# LAPPA-2020.net
KiCad netlist of a schematic drawn in Altium Designer
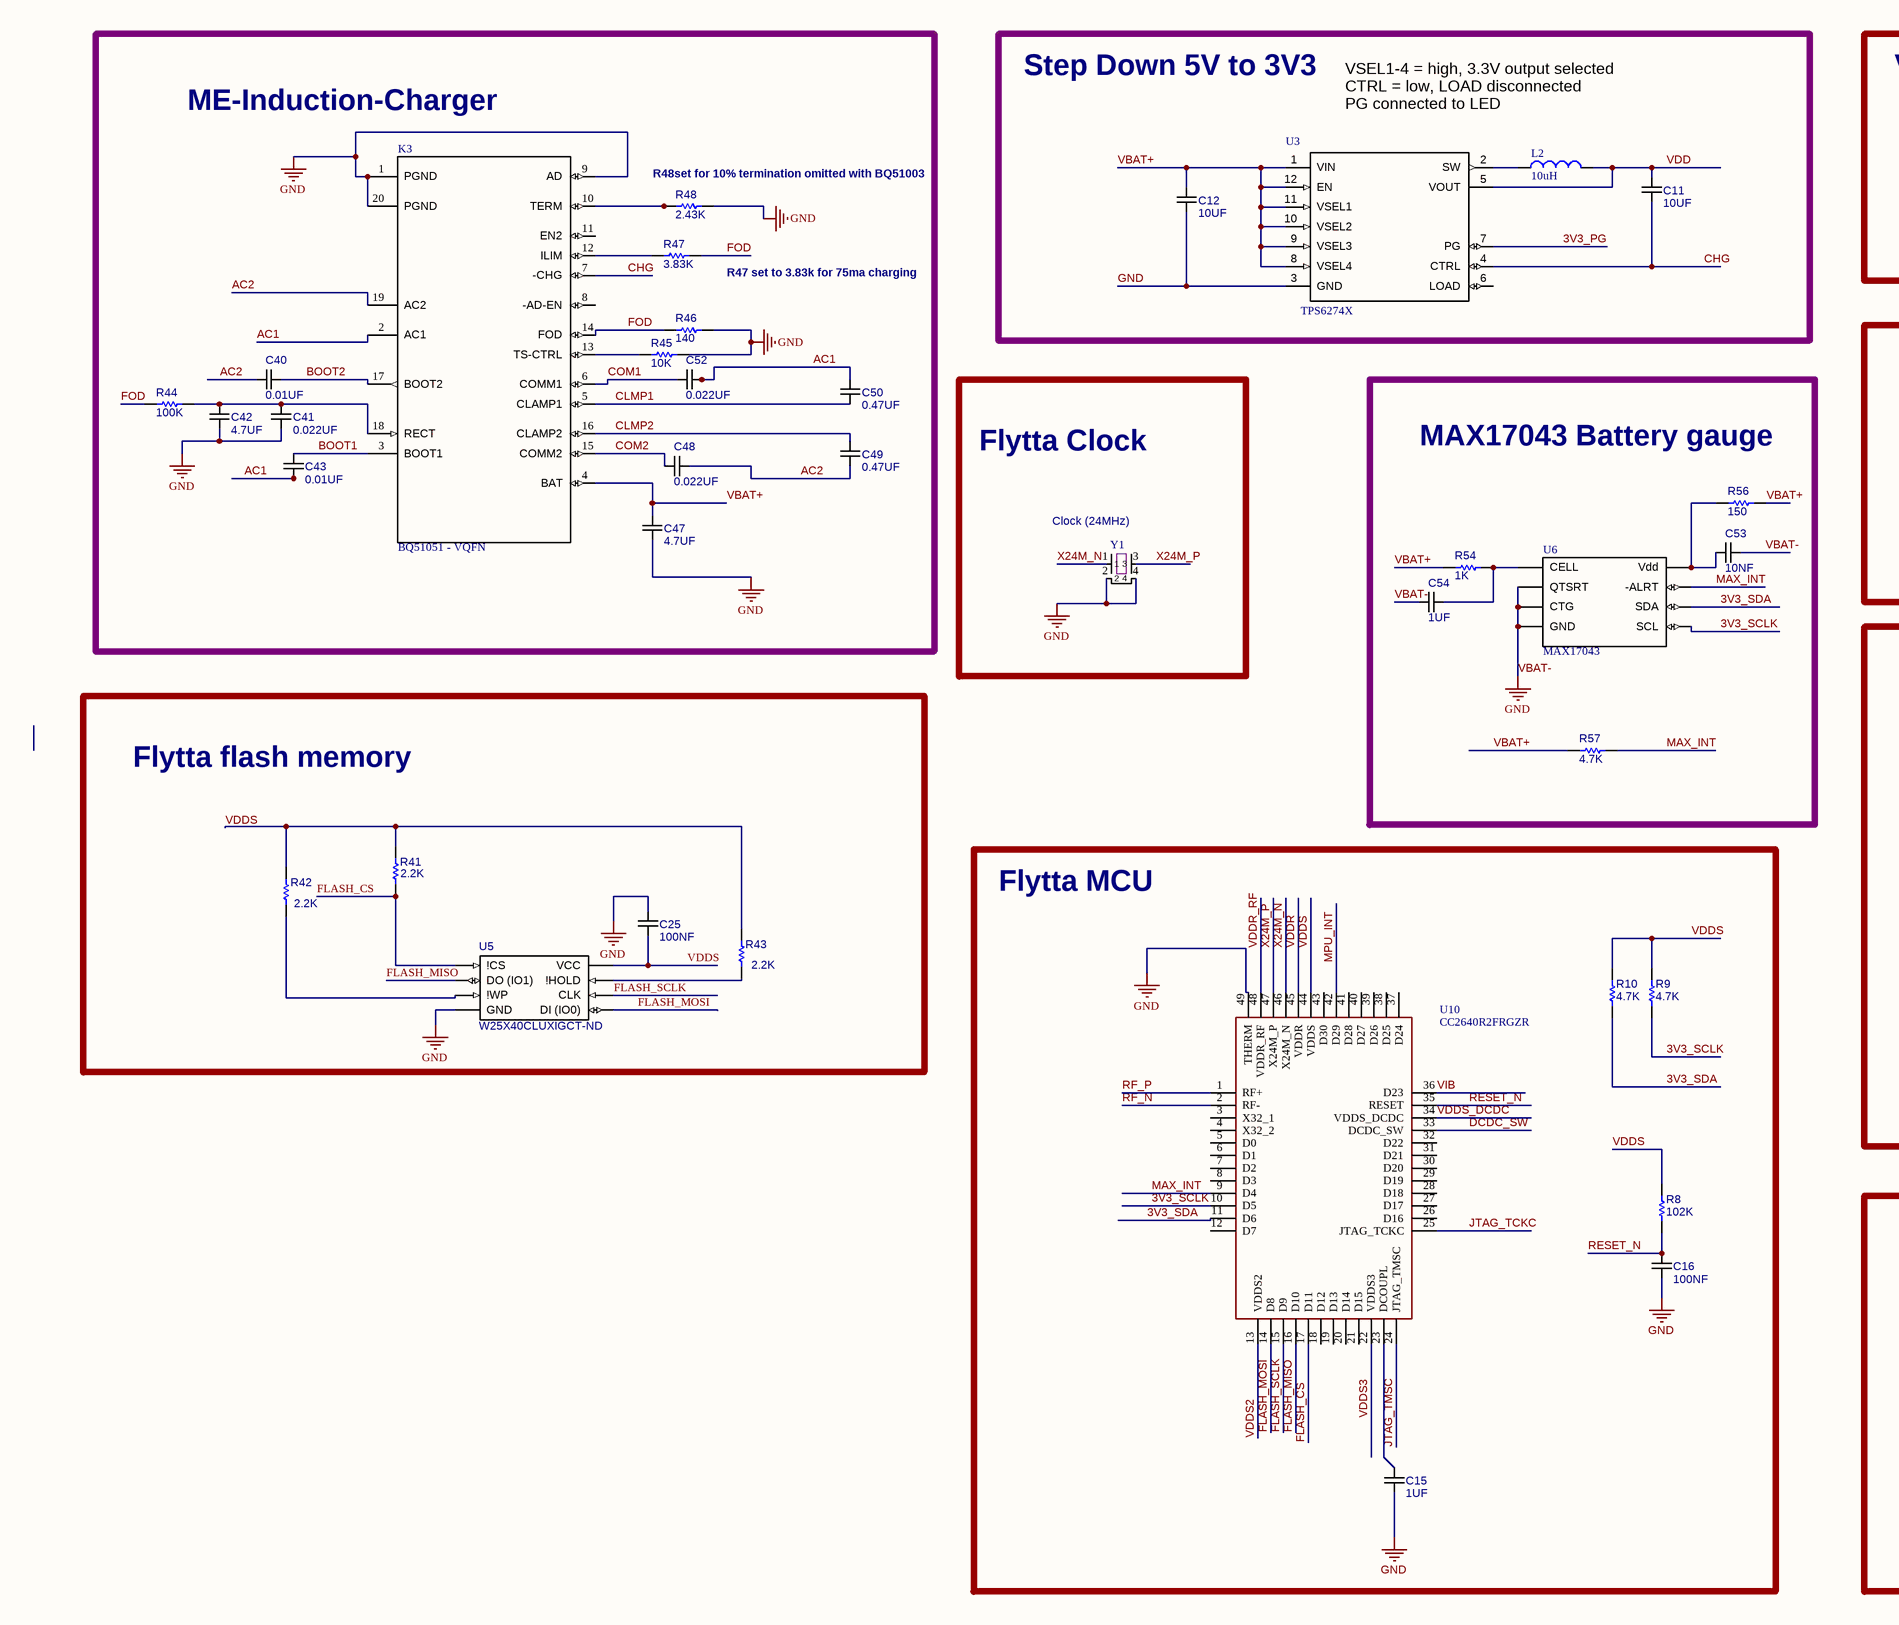
[diagram p0: LAPPA-2020.SchDoc, left]
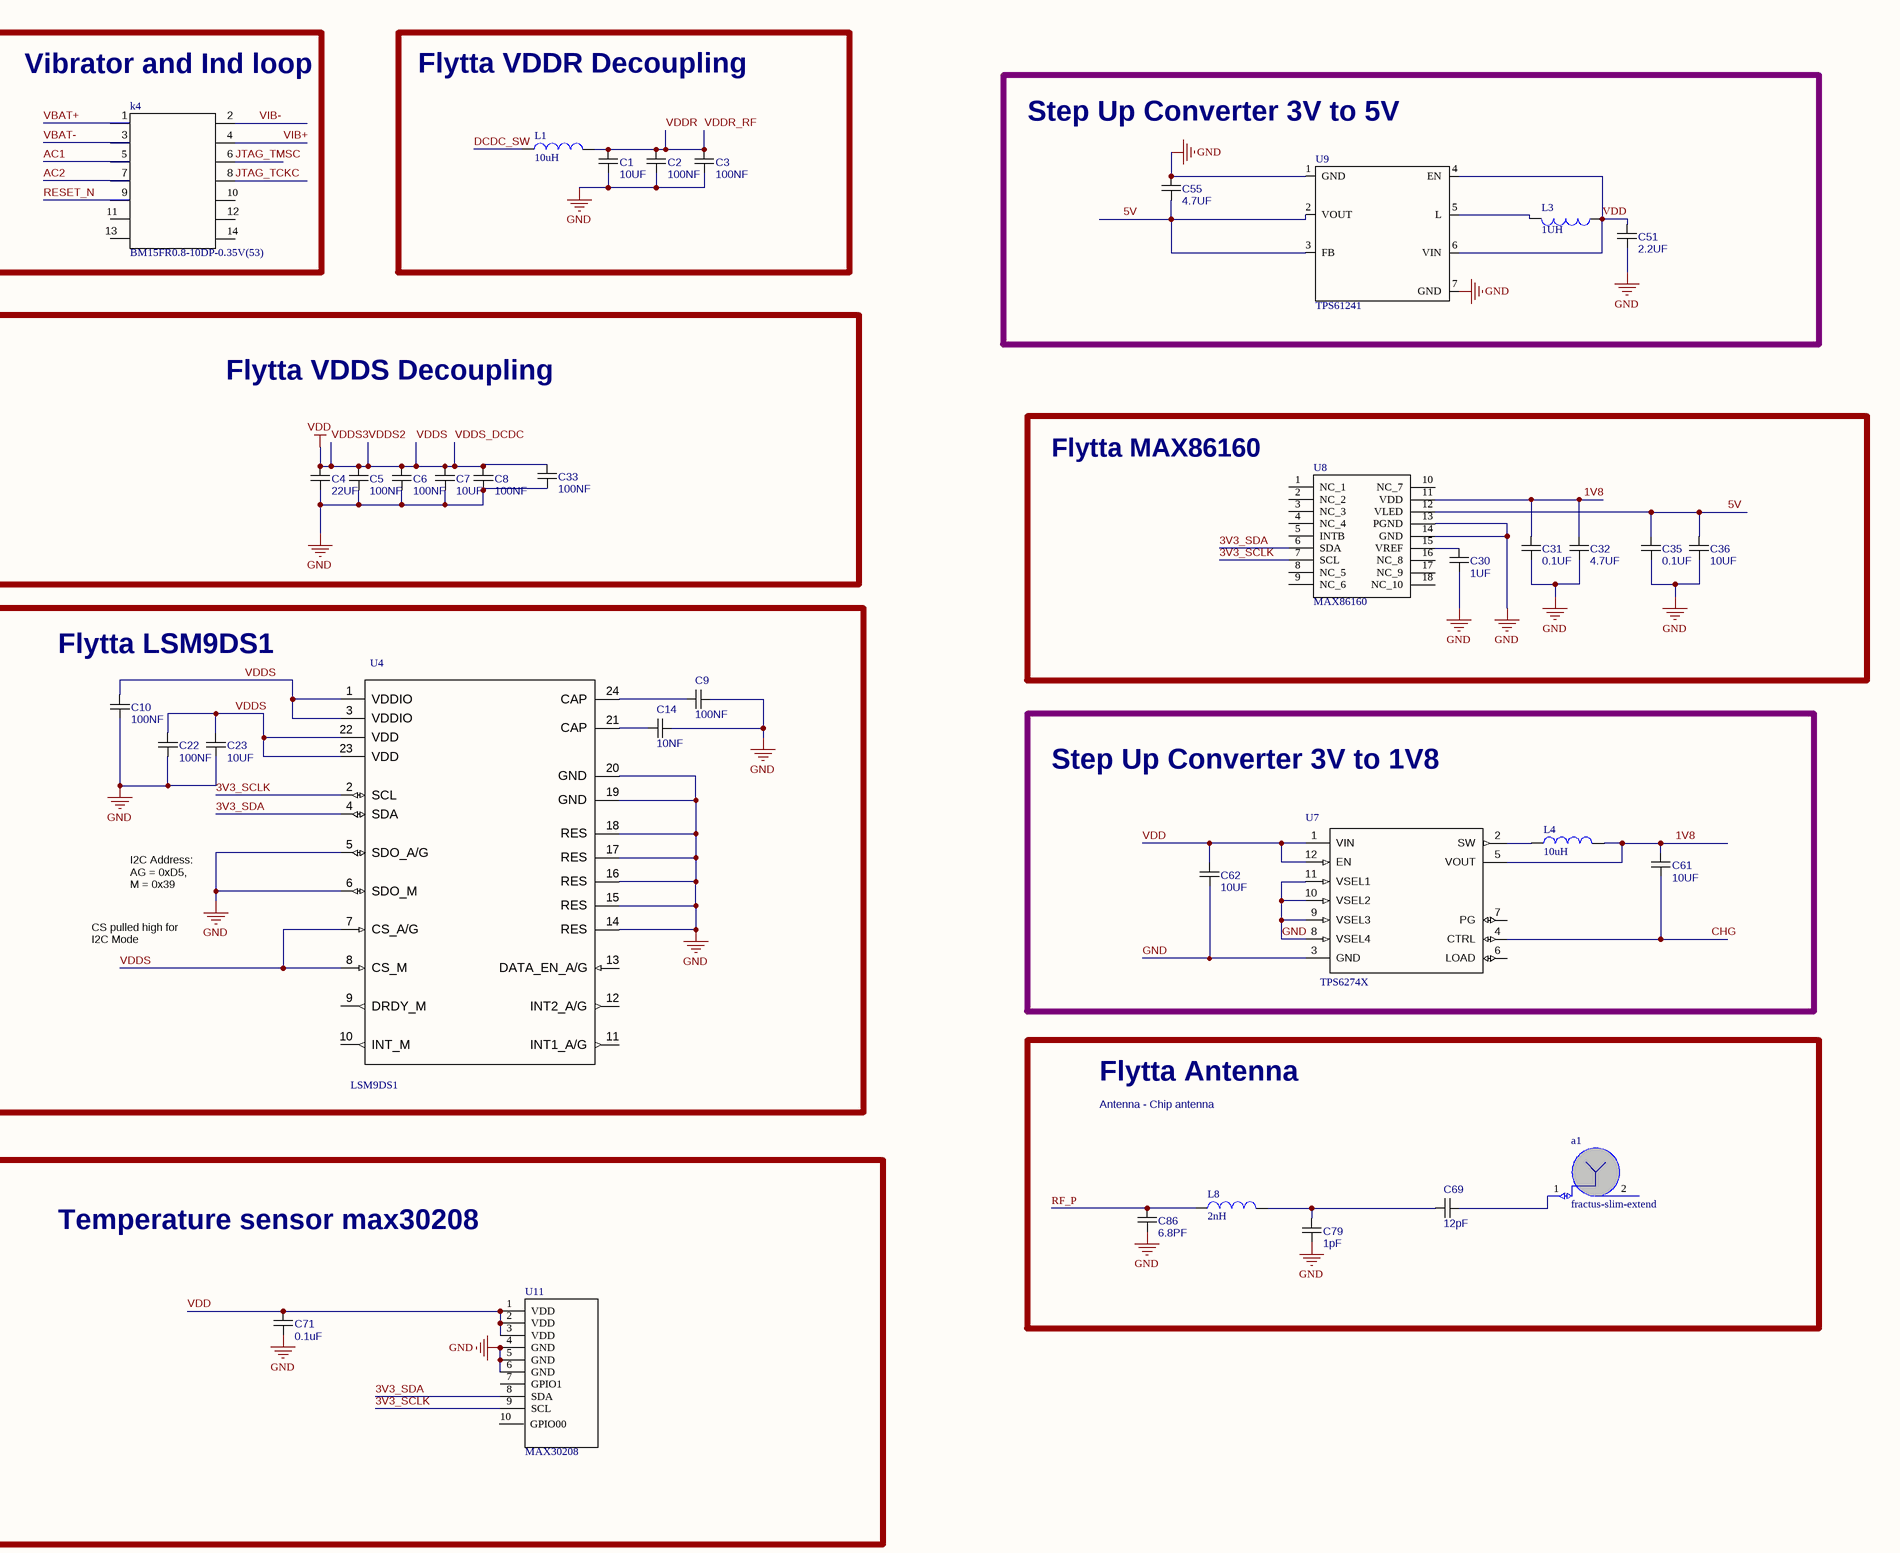
[diagram p1: LAPPA-2020.SchDoc, right]

(export (version "E")
  (design (tool "Eeschema 10.0.6"))
  (components
    (comp (ref "a1")
      (value "fractus-slim-extend")
      (footprint "fractus-chip-antenna")
      (description "fractus ti chip antenna")
      (libsource (lib "MedEngineSchematicLib") (part "fractus-chip-antenna"))
    )
    (comp (ref "C1")
      (value "10UF")
      (footprint "Passive (0402, 1005)")
      (description "Ceramic chip capacitor")
      (libsource (lib "MedEngineSchematicLib") (part "Capacitor"))
    )
    (comp (ref "C2")
      (value "100NF")
      (footprint "Passive (0402, 1005)")
      (description "Ceramic chip capacitor")
      (libsource (lib "MedEngineSchematicLib") (part "Capacitor"))
    )
    (comp (ref "C3")
      (value "100NF")
      (footprint "Passive (0402, 1005)")
      (description "Ceramic chip capacitor")
      (libsource (lib "MedEngineSchematicLib") (part "Capacitor"))
    )
    (comp (ref "C4")
      (value "22UF")
      (footprint "Passive (0402, 1005)")
      (description "Ceramic chip capacitor")
      (libsource (lib "MedEngineSchematicLib") (part "Capacitor"))
    )
    (comp (ref "C5")
      (value "100NF")
      (footprint "Passive (0402, 1005)")
      (description "Ceramic chip capacitor")
      (libsource (lib "MedEngineSchematicLib") (part "Capacitor"))
    )
    (comp (ref "C6")
      (value "100NF")
      (footprint "Passive (0402, 1005)")
      (description "Ceramic chip capacitor")
      (libsource (lib "MedEngineSchematicLib") (part "Capacitor"))
    )
    (comp (ref "C7")
      (value "10UF")
      (footprint "Passive (0402, 1005)")
      (description "Ceramic chip capacitor")
      (libsource (lib "MedEngineSchematicLib") (part "Capacitor"))
    )
    (comp (ref "C8")
      (value "100NF")
      (footprint "Passive (0402, 1005)")
      (description "Ceramic chip capacitor")
      (libsource (lib "MedEngineSchematicLib") (part "Capacitor"))
    )
    (comp (ref "C9")
      (value "100NF")
      (footprint "Passive (0402, 1005)")
      (description "Ceramic chip capacitor")
      (libsource (lib "MedEngineSchematicLib") (part "Capacitor"))
    )
    (comp (ref "C10")
      (value "100NF")
      (footprint "Passive (0402, 1005)")
      (description "Ceramic chip capacitor")
      (libsource (lib "MedEngineSchematicLib") (part "Capacitor"))
    )
    (comp (ref "C11")
      (value "10UF")
      (footprint "Passive (0402, 1005)")
      (description "Ceramic chip capacitor")
      (libsource (lib "MedEngineSchematicLib") (part "Capacitor"))
    )
    (comp (ref "C12")
      (value "10UF")
      (footprint "Passive (0402, 1005)")
      (description "Ceramic chip capacitor")
      (libsource (lib "MedEngineSchematicLib") (part "Capacitor"))
    )
    (comp (ref "C14")
      (value "10NF")
      (footprint "Passive (0402, 1005)")
      (description "Ceramic chip capacitor")
      (libsource (lib "MedEngineSchematicLib") (part "Capacitor"))
    )
    (comp (ref "C15")
      (value "1UF")
      (footprint "Passive (0402, 1005)")
      (description "Ceramic chip capacitor")
      (libsource (lib "MedEngineSchematicLib") (part "Capacitor"))
    )
    (comp (ref "C16")
      (value "100NF")
      (footprint "Passive (0402, 1005)")
      (description "Ceramic chip capacitor")
      (libsource (lib "MedEngineSchematicLib") (part "Capacitor"))
    )
    (comp (ref "C22")
      (value "100NF")
      (footprint "Passive (0402, 1005)")
      (description "Ceramic chip capacitor")
      (libsource (lib "MedEngineSchematicLib") (part "Capacitor"))
    )
    (comp (ref "C23")
      (value "10UF")
      (footprint "Passive (0402, 1005)")
      (description "Ceramic chip capacitor")
      (libsource (lib "MedEngineSchematicLib") (part "Capacitor"))
    )
    (comp (ref "C25")
      (value "100NF")
      (footprint "Passive (0402, 1005)")
      (description "Ceramic chip capacitor")
      (libsource (lib "MedEngineSchematicLib") (part "Capacitor"))
    )
    (comp (ref "C30")
      (value "1UF")
      (footprint "Passive (0402, 1005)")
      (description "Ceramic chip capacitor")
      (libsource (lib "MedEngineSchematicLib") (part "Capacitor"))
    )
    (comp (ref "C31")
      (value "0.1UF")
      (footprint "Passive (0402, 1005)")
      (description "Ceramic chip capacitor")
      (libsource (lib "MedEngineSchematicLib") (part "Capacitor"))
    )
    (comp (ref "C32")
      (value "4.7UF")
      (footprint "Passive (0402, 1005)")
      (description "Ceramic chip capacitor")
      (libsource (lib "MedEngineSchematicLib") (part "Capacitor"))
    )
    (comp (ref "C33")
      (value "100NF")
      (footprint "Passive (0402, 1005)")
      (description "Ceramic chip capacitor")
      (libsource (lib "MedEngineSchematicLib") (part "Capacitor"))
    )
    (comp (ref "C35")
      (value "0.1UF")
      (footprint "Passive (0402, 1005)")
      (description "Ceramic chip capacitor")
      (libsource (lib "MedEngineSchematicLib") (part "Capacitor"))
    )
    (comp (ref "C36")
      (value "10UF")
      (footprint "Passive (0402, 1005)")
      (description "Ceramic chip capacitor")
      (libsource (lib "MedEngineSchematicLib") (part "Capacitor"))
    )
    (comp (ref "C40")
      (value "0.01UF")
      (footprint "Passive (0402, 1005)")
      (description "Ceramic chip capacitor")
      (libsource (lib "MedEngineSchematicLib") (part "Capacitor"))
    )
    (comp (ref "C41")
      (value "0.022UF")
      (footprint "Passive (0402, 1005)")
      (description "Ceramic chip capacitor")
      (libsource (lib "MedEngineSchematicLib") (part "Capacitor"))
    )
    (comp (ref "C42")
      (value "4.7UF")
      (footprint "Passive (0402, 1005)")
      (description "Ceramic chip capacitor")
      (libsource (lib "MedEngineSchematicLib") (part "Capacitor"))
    )
    (comp (ref "C43")
      (value "0.01UF")
      (footprint "Passive (0402, 1005)")
      (description "Ceramic chip capacitor")
      (libsource (lib "MedEngineSchematicLib") (part "Capacitor"))
    )
    (comp (ref "C47")
      (value "4.7UF")
      (footprint "Passive (0402, 1005)")
      (description "Ceramic chip capacitor")
      (libsource (lib "MedEngineSchematicLib") (part "Capacitor"))
    )
    (comp (ref "C48")
      (value "0.022UF")
      (footprint "Passive (0402, 1005)")
      (description "Ceramic chip capacitor")
      (libsource (lib "MedEngineSchematicLib") (part "Capacitor"))
    )
    (comp (ref "C49")
      (value "0.47UF")
      (footprint "Passive (0402, 1005)")
      (description "Ceramic chip capacitor")
      (libsource (lib "MedEngineSchematicLib") (part "Capacitor"))
    )
    (comp (ref "C50")
      (value "0.47UF")
      (footprint "Passive (0402, 1005)")
      (description "Ceramic chip capacitor")
      (libsource (lib "MedEngineSchematicLib") (part "Capacitor"))
    )
    (comp (ref "C51")
      (value "2.2UF")
      (footprint "Passive (0402, 1005)")
      (description "Ceramic chip capacitor")
      (libsource (lib "MedEngineSchematicLib") (part "Capacitor"))
    )
    (comp (ref "C52")
      (value "0.022UF")
      (footprint "Passive (0402, 1005)")
      (description "Ceramic chip capacitor")
      (libsource (lib "MedEngineSchematicLib") (part "Capacitor"))
    )
    (comp (ref "C53")
      (value "10NF")
      (footprint "Passive (0402, 1005)")
      (description "Ceramic chip capacitor")
      (libsource (lib "MedEngineSchematicLib") (part "Capacitor"))
    )
    (comp (ref "C54")
      (value "1UF")
      (footprint "Passive (0402, 1005)")
      (description "Ceramic chip capacitor")
      (libsource (lib "MedEngineSchematicLib") (part "Capacitor"))
    )
    (comp (ref "C55")
      (value "4.7UF")
      (footprint "Passive (0402, 1005)")
      (description "Ceramic chip capacitor")
      (libsource (lib "MedEngineSchematicLib") (part "Capacitor"))
    )
    (comp (ref "C61")
      (value "10UF")
      (footprint "Passive (0402, 1005)")
      (description "Ceramic chip capacitor")
      (libsource (lib "MedEngineSchematicLib") (part "Capacitor"))
    )
    (comp (ref "C62")
      (value "10UF")
      (footprint "Passive (0402, 1005)")
      (description "Ceramic chip capacitor")
      (libsource (lib "MedEngineSchematicLib") (part "Capacitor"))
    )
    (comp (ref "C69")
      (value "12pF")
      (footprint "Passive (0402, 1005)")
      (description "Ceramic chip capacitor")
      (libsource (lib "MedEngineSchematicLib") (part "Capacitor"))
    )
    (comp (ref "C71")
      (value "0.1uF")
      (footprint "Passive (0402, 1005)")
      (description "Ceramic chip capacitor")
      (libsource (lib "MedEngineSchematicLib") (part "Capacitor"))
    )
    (comp (ref "C79")
      (value "1pF")
      (footprint "Passive (0402, 1005)")
      (description "Ceramic chip capacitor")
      (libsource (lib "MedEngineSchematicLib") (part "Capacitor"))
    )
    (comp (ref "C86")
      (value "6.8PF")
      (footprint "Passive (0402, 1005)")
      (description "Ceramic chip capacitor")
      (libsource (lib "MedEngineSchematicLib") (part "Capacitor"))
    )
    (comp (ref "K3")
      (value "BQ51051 - VQFN")
      (footprint "bq51051 - vqfn")
      (libsource (lib "MedEngineSchematicLib") (part "BQ51051 - VQFN"))
    )
    (comp (ref "k4")
      (value "BM15FR0.8-10DP-0.35V(53)")
      (footprint "BM15-Header")
      (libsource (lib "MedEngineSchematicLib") (part "bm15"))
    )
    (comp (ref "L1")
      (value "10uH")
      (footprint "Passive (0603, 1608)")
      (description "Inductor")
      (fields (field (name "PUBLISHER") "Altium Limited"))
      (libsource (lib "MedEngineSchematicLib") (part "Inductor"))
    )
    (comp (ref "L2")
      (value "10uH")
      (footprint "Passive (0603, 1608)")
      (description "Inductor")
      (fields (field (name "PUBLISHER") "Altium Limited"))
      (libsource (lib "MedEngineSchematicLib") (part "Inductor"))
    )
    (comp (ref "L3")
      (value "1UH")
      (footprint "Passive (0603, 1608)")
      (description "Inductor")
      (fields (field (name "PUBLISHER") "Altium Limited"))
      (libsource (lib "MedEngineSchematicLib") (part "Inductor"))
    )
    (comp (ref "L4")
      (value "10uH")
      (footprint "Passive (0603, 1608)")
      (description "Inductor")
      (fields (field (name "PUBLISHER") "Altium Limited"))
      (libsource (lib "MedEngineSchematicLib") (part "Inductor"))
    )
    (comp (ref "L8")
      (value "2nH")
      (footprint "Passive (0402, 1005)")
      (description "Inductor")
      (fields (field (name "PUBLISHER") "Altium Limited"))
      (libsource (lib "MedEngineSchematicLib") (part "Inductor"))
    )
    (comp (ref "R8")
      (value "102K")
      (footprint "Passive (0402, 1005)")
      (description "Resistor")
      (libsource (lib "MedEngineSchematicLib") (part "Resistor"))
    )
    (comp (ref "R9")
      (value "4.7K")
      (footprint "Passive (0402, 1005)")
      (description "Resistor")
      (libsource (lib "MedEngineSchematicLib") (part "Resistor"))
    )
    (comp (ref "R10")
      (value "4.7K")
      (footprint "Passive (0402, 1005)")
      (description "Resistor")
      (libsource (lib "MedEngineSchematicLib") (part "Resistor"))
    )
    (comp (ref "R41")
      (value "2.2K")
      (footprint "Passive (0402, 1005)")
      (description "Resistor")
      (libsource (lib "MedEngineSchematicLib") (part "Resistor"))
    )
    (comp (ref "R42")
      (value "2.2K")
      (footprint "Passive (0402, 1005)")
      (description "Resistor")
      (libsource (lib "MedEngineSchematicLib") (part "Resistor"))
    )
    (comp (ref "R43")
      (value "2.2K")
      (footprint "Passive (0402, 1005)")
      (description "Resistor")
      (libsource (lib "MedEngineSchematicLib") (part "Resistor"))
    )
    (comp (ref "R44")
      (value "100K")
      (footprint "Passive (0402, 1005)")
      (description "Resistor")
      (libsource (lib "MedEngineSchematicLib") (part "Resistor"))
    )
    (comp (ref "R45")
      (value "10K")
      (footprint "Passive (0402, 1005)")
      (description "Resistor")
      (libsource (lib "MedEngineSchematicLib") (part "Resistor"))
    )
    (comp (ref "R46")
      (value "140")
      (footprint "Passive (0402, 1005)")
      (description "Resistor")
      (libsource (lib "MedEngineSchematicLib") (part "Resistor"))
    )
    (comp (ref "R47")
      (value "3.83K")
      (footprint "Passive (0402, 1005)")
      (description "Resistor")
      (libsource (lib "MedEngineSchematicLib") (part "Resistor"))
    )
    (comp (ref "R48")
      (value "2.43K")
      (footprint "Passive (0402, 1005)")
      (description "Resistor")
      (libsource (lib "MedEngineSchematicLib") (part "Resistor"))
    )
    (comp (ref "R54")
      (value "1K")
      (footprint "Passive (0402, 1005)")
      (description "Resistor")
      (libsource (lib "MedEngineSchematicLib") (part "Resistor"))
    )
    (comp (ref "R56")
      (value "150")
      (footprint "Passive (0402, 1005)")
      (description "Resistor")
      (libsource (lib "MedEngineSchematicLib") (part "Resistor"))
    )
    (comp (ref "R57")
      (value "4.7K")
      (footprint "Passive (0402, 1005)")
      (description "Resistor")
      (libsource (lib "MedEngineSchematicLib") (part "Resistor"))
    )
    (comp (ref "U3")
      (value "TPS6274X")
      (footprint "TPS6274")
      (description "Step down converter")
      (libsource (lib "MedEngineSchematicLib") (part "TPS6274X"))
    )
    (comp (ref "U4")
      (value "LSM9DS1")
      (footprint "LSM9DS1")
      (description "9DOF, Accel, Gyro, Mag")
      (fields (field (name "MF") "Microchip") (field (name "MP") "MCP73871-3CAI/ML"))
      (libsource (lib "MedEngineSchematicLib") (part "LSM9DS1"))
    )
    (comp (ref "U5")
      (value "W25X40CLUXIGCT-ND")
      (footprint "USON 2x3")
      (libsource (lib "MedEngineSchematicLib") (part "W25X40CLUXIGCT-ND"))
    )
    (comp (ref "U6")
      (value "MAX17043")
      (footprint "MAX17043")
      (description "I2C battery gauge")
      (libsource (lib "MedEngineSchematicLib") (part "MAX17043"))
    )
    (comp (ref "U7")
      (value "TPS6274X")
      (footprint "TPS6274")
      (description "Step down converter")
      (libsource (lib "MedEngineSchematicLib") (part "TPS6274X"))
    )
    (comp (ref "U8")
      (value "MAX86160")
      (footprint "MAX86160")
      (libsource (lib "MedEngineSchematicLib") (part "MAX86160"))
    )
    (comp (ref "U9")
      (value "TPS61241")
      (footprint "TPS61241")
      (libsource (lib "MedEngineSchematicLib") (part "TPS61241"))
    )
    (comp (ref "U10")
      (value "CC2640R2FRGZR")
      (footprint "CC2640R2FRGZR")
      (libsource (lib "MedEngineSchematicLib") (part "CC2640R2FRGZR"))
    )
    (comp (ref "U11")
      (value "MAX30208")
      (footprint "MAX30208")
      (libsource (lib "MedEngineSchematicLib") (part "MAX30208"))
    )
    (comp (ref "Y1")
      (value "24MHz crystal")
      (footprint "TSX-3225")
      (libsource (lib "TSX3225") (part "TSX-3225"))
    )
  )
  (nets
    (net (code "1") (name "/1V8") (class "Default")
      (node (ref "C31") (pin "2") (pinfunction "2_2") (pintype "passive"))
      (node (ref "C32") (pin "2") (pinfunction "2_2") (pintype "passive"))
      (node (ref "C61") (pin "2") (pinfunction "2_2") (pintype "passive"))
      (node (ref "L4") (pin "2") (pinfunction "2_2") (pintype "passive"))
      (node (ref "U7") (pin "5") (pinfunction "VOUT_5") (pintype "power_in"))
      (node (ref "U8") (pin "11") (pinfunction "VDD_11") (pintype "passive"))
    )
    (net (code "2") (name "/3V3_PG") (class "Default")
      (node (ref "U3") (pin "7") (pinfunction "PG_7") (pintype "bidirectional"))
    )
    (net (code "3") (name "/3V3_SCLK") (class "Default")
      (node (ref "R9") (pin "1") (pinfunction "1_1") (pintype "passive"))
      (node (ref "U10") (pin "10") (pinfunction "D5_10") (pintype "passive"))
      (node (ref "U11") (pin "9") (pinfunction "SCL_9") (pintype "passive"))
      (node (ref "U4") (pin "2") (pinfunction "SCL_2") (pintype "bidirectional"))
      (node (ref "U6") (pin "A2") (pinfunction "SCL_A2") (pintype "bidirectional"))
      (node (ref "U8") (pin "7") (pinfunction "SCL_7") (pintype "passive"))
    )
    (net (code "4") (name "/3V3_SDA") (class "Default")
      (node (ref "R10") (pin "1") (pinfunction "1_1") (pintype "passive"))
      (node (ref "U10") (pin "11") (pinfunction "D6_11") (pintype "passive"))
      (node (ref "U11") (pin "8") (pinfunction "SDA_8") (pintype "passive"))
      (node (ref "U4") (pin "4") (pinfunction "SDA_4") (pintype "bidirectional"))
      (node (ref "U6") (pin "A1") (pinfunction "SDA_A1") (pintype "bidirectional"))
      (node (ref "U8") (pin "6") (pinfunction "SDA_6") (pintype "passive"))
    )
    (net (code "5") (name "/5V") (class "Default")
      (node (ref "C35") (pin "2") (pinfunction "2_2") (pintype "passive"))
      (node (ref "C36") (pin "2") (pinfunction "2_2") (pintype "passive"))
      (node (ref "C55") (pin "1") (pinfunction "1_1") (pintype "passive"))
      (node (ref "U8") (pin "12") (pinfunction "VLED_12") (pintype "passive"))
      (node (ref "U9") (pin "2") (pinfunction "VOUT_2") (pintype "passive"))
      (node (ref "U9") (pin "3") (pinfunction "FB_3") (pintype "passive"))
    )
    (net (code "6") (name "/AC1") (class "Default")
      (node (ref "C43") (pin "2") (pinfunction "2_2") (pintype "passive"))
      (node (ref "C50") (pin "1") (pinfunction "1_1") (pintype "passive"))
      (node (ref "C52") (pin "2") (pinfunction "2_2") (pintype "passive"))
      (node (ref "K3") (pin "2") (pinfunction "AC1_2") (pintype "passive"))
      (node (ref "k4") (pin "5") (pintype "power_in"))
    )
    (net (code "7") (name "/AC2") (class "Default")
      (node (ref "C40") (pin "2") (pinfunction "2_2") (pintype "passive"))
      (node (ref "C48") (pin "2") (pinfunction "2_2") (pintype "passive"))
      (node (ref "C49") (pin "2") (pinfunction "2_2") (pintype "passive"))
      (node (ref "K3") (pin "19") (pinfunction "AC2_19") (pintype "power_in"))
      (node (ref "k4") (pin "7") (pintype "passive"))
    )
    (net (code "8") (name "/BOOT1") (class "Default")
      (node (ref "C43") (pin "1") (pinfunction "1_1") (pintype "passive"))
      (node (ref "K3") (pin "3") (pinfunction "BOOT1_3") (pintype "passive"))
    )
    (net (code "9") (name "/BOOT2") (class "Default")
      (node (ref "C40") (pin "1") (pinfunction "1_1") (pintype "passive"))
      (node (ref "K3") (pin "17") (pinfunction "BOOT2_17") (pintype "output"))
    )
    (net (code "10") (name "/CHG") (class "Default")
      (node (ref "C11") (pin "1") (pinfunction "1_1") (pintype "passive"))
      (node (ref "C61") (pin "1") (pinfunction "1_1") (pintype "passive"))
      (node (ref "K3") (pin "7") (pinfunction "-CHG_7") (pintype "bidirectional"))
      (node (ref "U3") (pin "4") (pinfunction "CTRL_4") (pintype "bidirectional"))
      (node (ref "U7") (pin "4") (pinfunction "CTRL_4") (pintype "bidirectional"))
    )
    (net (code "11") (name "/CLMP1") (class "Default")
      (node (ref "C50") (pin "2") (pinfunction "2_2") (pintype "passive"))
      (node (ref "K3") (pin "5") (pinfunction "CLAMP1_5") (pintype "bidirectional"))
    )
    (net (code "12") (name "/CLMP2") (class "Default")
      (node (ref "C49") (pin "1") (pinfunction "1_1") (pintype "passive"))
      (node (ref "K3") (pin "16") (pinfunction "CLAMP2_16") (pintype "bidirectional"))
    )
    (net (code "13") (name "/COM1") (class "Default")
      (node (ref "C52") (pin "1") (pinfunction "1_1") (pintype "passive"))
      (node (ref "K3") (pin "6") (pinfunction "COMM1_6") (pintype "bidirectional"))
    )
    (net (code "14") (name "/COM2") (class "Default")
      (node (ref "C48") (pin "1") (pinfunction "1_1") (pintype "passive"))
      (node (ref "K3") (pin "15") (pinfunction "COMM2_15") (pintype "bidirectional"))
    )
    (net (code "15") (name "/DCDC_SW") (class "Default")
      (node (ref "L1") (pin "1") (pinfunction "1_1") (pintype "passive"))
      (node (ref "U10") (pin "33") (pinfunction "DCDC_SW_33") (pintype "passive"))
    )
    (net (code "16") (name "/FLASH_CS") (class "Default")
      (node (ref "R41") (pin "1") (pinfunction "1_1") (pintype "passive"))
      (node (ref "U10") (pin "17") (pinfunction "D11_17") (pintype "passive"))
      (node (ref "U5") (pin "1") (pinfunction "!CS_1") (pintype "input"))
    )
    (net (code "17") (name "/FLASH_MISO") (class "Default")
      (node (ref "U10") (pin "16") (pinfunction "D10_16") (pintype "passive"))
      (node (ref "U5") (pin "2") (pinfunction "DO_(IO1)_2") (pintype "bidirectional"))
    )
    (net (code "18") (name "/FLASH_MOSI") (class "Default")
      (node (ref "U10") (pin "14") (pinfunction "D8_14") (pintype "passive"))
      (node (ref "U5") (pin "5") (pinfunction "DI_(IO0)_5") (pintype "bidirectional"))
    )
    (net (code "19") (name "/FLASH_SCLK") (class "Default")
      (node (ref "U10") (pin "15") (pinfunction "D9_15") (pintype "passive"))
      (node (ref "U5") (pin "6") (pinfunction "CLK_6") (pintype "input"))
    )
    (net (code "20") (name "/FOD") (class "Default")
      (node (ref "K3") (pin "14") (pinfunction "FOD_14") (pintype "bidirectional"))
      (node (ref "R44") (pin "2") (pinfunction "2_2") (pintype "passive"))
      (node (ref "R46") (pin "2") (pinfunction "2_2") (pintype "passive"))
      (node (ref "R47") (pin "1") (pinfunction "1_1") (pintype "passive"))
    )
    (net (code "21") (name "/JTAG_TCKC") (class "Default")
      (node (ref "U10") (pin "25") (pinfunction "JTAG_TCKC_25") (pintype "passive"))
      (node (ref "k4") (pin "8") (pintype "power_in"))
    )
    (net (code "22") (name "/JTAG_TMSC") (class "Default")
      (node (ref "U10") (pin "24") (pinfunction "JTAG_TMSC_24") (pintype "passive"))
      (node (ref "k4") (pin "6") (pintype "power_in"))
    )
    (net (code "23") (name "/MAX_INT") (class "Default")
      (node (ref "R57") (pin "1") (pinfunction "1_1") (pintype "passive"))
      (node (ref "U10") (pin "9") (pinfunction "D4_9") (pintype "passive"))
      (node (ref "U6") (pin "C1") (pinfunction "-ALRT_C1") (pintype "bidirectional"))
    )
    (net (code "24") (name "/MPU_INT") (class "Default")
      (node (ref "U10") (pin "42") (pinfunction "D29_42") (pintype "passive"))
    )
    (net (code "25") (name "/RESET_N") (class "Default")
      (node (ref "C16") (pin "2") (pinfunction "2_2") (pintype "passive"))
      (node (ref "R8") (pin "1") (pinfunction "1_1") (pintype "passive"))
      (node (ref "U10") (pin "35") (pinfunction "RESET_35") (pintype "passive"))
      (node (ref "k4") (pin "9") (pintype "passive"))
    )
    (net (code "26") (name "/RF_N") (class "Default")
      (node (ref "U10") (pin "2") (pinfunction "RF-_2") (pintype "passive"))
    )
    (net (code "27") (name "/RF_P") (class "Default")
      (node (ref "C86") (pin "2") (pinfunction "2_2") (pintype "passive"))
      (node (ref "L8") (pin "1") (pinfunction "1_1") (pintype "passive"))
      (node (ref "U10") (pin "1") (pinfunction "RF+_1") (pintype "passive"))
    )
    (net (code "28") (name "/VBAT+") (class "Default")
      (node (ref "C12") (pin "2") (pinfunction "2_2") (pintype "passive"))
      (node (ref "C47") (pin "1") (pinfunction "1_1") (pintype "passive"))
      (node (ref "K3") (pin "4") (pinfunction "BAT_4") (pintype "bidirectional"))
      (node (ref "R54") (pin "2") (pinfunction "2_2") (pintype "passive"))
      (node (ref "R56") (pin "1") (pinfunction "1_1") (pintype "passive"))
      (node (ref "R57") (pin "2") (pinfunction "2_2") (pintype "passive"))
      (node (ref "U3") (pin "1") (pinfunction "VIN_1") (pintype "power_in"))
      (node (ref "U3") (pin "10") (pinfunction "VSEL2_10") (pintype "input"))
      (node (ref "U3") (pin "11") (pinfunction "VSEL1_11") (pintype "input"))
      (node (ref "U3") (pin "12") (pinfunction "EN_12") (pintype "input"))
      (node (ref "U3") (pin "8") (pinfunction "VSEL4_8") (pintype "input"))
      (node (ref "U3") (pin "9") (pinfunction "VSEL3_9") (pintype "input"))
      (node (ref "k4") (pin "1") (pintype "passive"))
    )
    (net (code "29") (name "/VDDR") (class "Default")
      (node (ref "C1") (pin "2") (pinfunction "2_2") (pintype "passive"))
      (node (ref "C2") (pin "2") (pinfunction "2_2") (pintype "passive"))
      (node (ref "C3") (pin "2") (pinfunction "2_2") (pintype "passive"))
      (node (ref "L1") (pin "2") (pinfunction "2_2") (pintype "passive"))
      (node (ref "U10") (pin "45") (pinfunction "VDDR_45") (pintype "passive"))
      (node (ref "U10") (pin "48") (pinfunction "VDDR_RF_48") (pintype "passive"))
    )
    (net (code "30") (name "/VIB") (class "Default")
      (node (ref "U10") (pin "36") (pinfunction "D23_36") (pintype "passive"))
    )
    (net (code "31") (name "/VIB+") (class "Default") (node (ref "k4") (pin "4") (pintype "passive")))
    (net (code "32") (name "/VIB-") (class "Default") (node (ref "k4") (pin "2") (pintype "power_in")))
    (net (code "33") (name "/X24M_N") (class "Default")
      (node (ref "U10") (pin "46") (pinfunction "X24M_N_46") (pintype "passive"))
      (node (ref "Y1") (pin "1") (pinfunction "1_1") (pintype "passive"))
    )
    (net (code "34") (name "/X24M_P") (class "Default")
      (node (ref "U10") (pin "47") (pinfunction "X24M_P_47") (pintype "passive"))
      (node (ref "Y1") (pin "3") (pinfunction "3_3") (pintype "passive"))
    )
    (net (code "35") (name "GND") (class "Default")
      (node (ref "C1") (pin "1") (pinfunction "1_1") (pintype "passive"))
      (node (ref "C10") (pin "2") (pinfunction "2_2") (pintype "passive"))
      (node (ref "C12") (pin "1") (pinfunction "1_1") (pintype "passive"))
      (node (ref "C14") (pin "1") (pinfunction "1_1") (pintype "passive"))
      (node (ref "C15") (pin "1") (pinfunction "1_1") (pintype "passive"))
      (node (ref "C16") (pin "1") (pinfunction "1_1") (pintype "passive"))
      (node (ref "C2") (pin "1") (pinfunction "1_1") (pintype "passive"))
      (node (ref "C22") (pin "1") (pinfunction "1_1") (pintype "passive"))
      (node (ref "C23") (pin "1") (pinfunction "1_1") (pintype "passive"))
      (node (ref "C25") (pin "2") (pinfunction "2_2") (pintype "passive"))
      (node (ref "C3") (pin "1") (pinfunction "1_1") (pintype "passive"))
      (node (ref "C30") (pin "1") (pinfunction "1_1") (pintype "passive"))
      (node (ref "C31") (pin "1") (pinfunction "1_1") (pintype "passive"))
      (node (ref "C32") (pin "1") (pinfunction "1_1") (pintype "passive"))
      (node (ref "C33") (pin "1") (pinfunction "1_1") (pintype "passive"))
      (node (ref "C35") (pin "1") (pinfunction "1_1") (pintype "passive"))
      (node (ref "C36") (pin "1") (pinfunction "1_1") (pintype "passive"))
      (node (ref "C4") (pin "1") (pinfunction "1_1") (pintype "passive"))
      (node (ref "C41") (pin "2") (pinfunction "2_2") (pintype "passive"))
      (node (ref "C42") (pin "2") (pinfunction "2_2") (pintype "passive"))
      (node (ref "C47") (pin "2") (pinfunction "2_2") (pintype "passive"))
      (node (ref "C5") (pin "1") (pinfunction "1_1") (pintype "passive"))
      (node (ref "C51") (pin "1") (pinfunction "1_1") (pintype "passive"))
      (node (ref "C53") (pin "2") (pinfunction "2_2") (pintype "passive"))
      (node (ref "C54") (pin "1") (pinfunction "1_1") (pintype "passive"))
      (node (ref "C55") (pin "2") (pinfunction "2_2") (pintype "passive"))
      (node (ref "C6") (pin "1") (pinfunction "1_1") (pintype "passive"))
      (node (ref "C62") (pin "1") (pinfunction "1_1") (pintype "passive"))
      (node (ref "C7") (pin "1") (pinfunction "1_1") (pintype "passive"))
      (node (ref "C71") (pin "1") (pinfunction "1_1") (pintype "passive"))
      (node (ref "C79") (pin "1") (pinfunction "1_1") (pintype "passive"))
      (node (ref "C8") (pin "1") (pinfunction "1_1") (pintype "passive"))
      (node (ref "C86") (pin "1") (pinfunction "1_1") (pintype "passive"))
      (node (ref "C9") (pin "1") (pinfunction "1_1") (pintype "passive"))
      (node (ref "K3") (pin "1") (pinfunction "PGND_1") (pintype "power_in"))
      (node (ref "K3") (pin "20") (pinfunction "PGND_20") (pintype "power_in"))
      (node (ref "K3") (pin "9") (pinfunction "AD_9") (pintype "bidirectional"))
      (node (ref "R45") (pin "1") (pinfunction "1_1") (pintype "passive"))
      (node (ref "R46") (pin "1") (pinfunction "1_1") (pintype "passive"))
      (node (ref "R48") (pin "1") (pinfunction "1_1") (pintype "passive"))
      (node (ref "U10") (pin "49") (pinfunction "THERM_49") (pintype "passive"))
      (node (ref "U11") (pin "4") (pinfunction "GND_4") (pintype "passive"))
      (node (ref "U11") (pin "5") (pinfunction "GND_5") (pintype "passive"))
      (node (ref "U11") (pin "6") (pinfunction "GND_6") (pintype "passive"))
      (node (ref "U3") (pin "3") (pinfunction "GND_3") (pintype "power_in"))
      (node (ref "U4") (pin "14") (pinfunction "RES_14") (pintype "passive"))
      (node (ref "U4") (pin "15") (pinfunction "RES_15") (pintype "passive"))
      (node (ref "U4") (pin "16") (pinfunction "RES_16") (pintype "passive"))
      (node (ref "U4") (pin "17") (pinfunction "RES_17") (pintype "passive"))
      (node (ref "U4") (pin "18") (pinfunction "RES_18") (pintype "passive"))
      (node (ref "U4") (pin "19") (pinfunction "GND_19") (pintype "passive"))
      (node (ref "U4") (pin "20") (pinfunction "GND_20") (pintype "passive"))
      (node (ref "U4") (pin "5") (pinfunction "SDO_A/G_5") (pintype "bidirectional"))
      (node (ref "U4") (pin "6") (pinfunction "SDO_M_6") (pintype "bidirectional"))
      (node (ref "U5") (pin "4") (pinfunction "GND_4") (pintype "power_in"))
      (node (ref "U6") (pin "A3") (pinfunction "CTG_A3") (pintype "power_in"))
      (node (ref "U6") (pin "B1") (pinfunction "QTSRT_B1") (pintype "power_in"))
      (node (ref "U6") (pin "C3") (pinfunction "GND_C3") (pintype "power_in"))
      (node (ref "U7") (pin "10") (pinfunction "VSEL2_10") (pintype "input"))
      (node (ref "U7") (pin "11") (pinfunction "VSEL1_11") (pintype "input"))
      (node (ref "U7") (pin "3") (pinfunction "GND_3") (pintype "power_in"))
      (node (ref "U7") (pin "8") (pinfunction "VSEL4_8") (pintype "input"))
      (node (ref "U7") (pin "9") (pinfunction "VSEL3_9") (pintype "input"))
      (node (ref "U8") (pin "13") (pinfunction "PGND_13") (pintype "passive"))
      (node (ref "U8") (pin "14") (pinfunction "GND_14") (pintype "passive"))
      (node (ref "U9") (pin "1") (pinfunction "GND_1") (pintype "passive"))
      (node (ref "U9") (pin "7") (pinfunction "GND_7") (pintype "passive"))
      (node (ref "Y1") (pin "2") (pinfunction "2_2") (pintype "passive"))
      (node (ref "Y1") (pin "4") (pinfunction "4_4") (pintype "passive"))
      (node (ref "k4") (pin "3") (pintype "passive"))
    )
    (net (code "36") (name "Net-(C9-Pad2)") (class "Default")
      (node (ref "C9") (pin "2") (pinfunction "2_2") (pintype "passive"))
      (node (ref "U4") (pin "24") (pinfunction "CAP_24") (pintype "passive"))
    )
    (net (code "37") (name "Net-(C14-Pad2)") (class "Default")
      (node (ref "C14") (pin "2") (pinfunction "2_2") (pintype "passive"))
      (node (ref "U4") (pin "21") (pinfunction "CAP_21") (pintype "passive"))
    )
    (net (code "38") (name "Net-(C69-Pad2)") (class "Default")
      (node (ref "C69") (pin "2") (pinfunction "2_2") (pintype "passive"))
      (node (ref "C79") (pin "2") (pinfunction "2_2") (pintype "passive"))
      (node (ref "L8") (pin "2") (pinfunction "2_2") (pintype "passive"))
    )
    (net (code "39") (name "Net-(K3-ILIM)") (class "Default")
      (node (ref "K3") (pin "12") (pinfunction "ILIM_12") (pintype "bidirectional"))
      (node (ref "R47") (pin "2") (pinfunction "2_2") (pintype "passive"))
    )
    (net (code "40") (name "Net-(K3-RECT)") (class "Default")
      (node (ref "C41") (pin "1") (pinfunction "1_1") (pintype "passive"))
      (node (ref "C42") (pin "1") (pinfunction "1_1") (pintype "passive"))
      (node (ref "K3") (pin "18") (pinfunction "RECT_18") (pintype "input"))
      (node (ref "R44") (pin "1") (pinfunction "1_1") (pintype "passive"))
    )
    (net (code "41") (name "Net-(K3-TERM)") (class "Default")
      (node (ref "K3") (pin "10") (pinfunction "TERM_10") (pintype "bidirectional"))
      (node (ref "R48") (pin "2") (pinfunction "2_2") (pintype "passive"))
    )
    (net (code "42") (name "Net-(K3-TS-CTRL)") (class "Default")
      (node (ref "K3") (pin "13") (pinfunction "TS-CTRL_13") (pintype "bidirectional"))
      (node (ref "R45") (pin "2") (pinfunction "2_2") (pintype "passive"))
    )
    (net (code "43") (name "Net-(U3-SW)") (class "Default")
      (node (ref "L2") (pin "1") (pinfunction "1_1") (pintype "passive"))
      (node (ref "U3") (pin "2") (pinfunction "SW_2") (pintype "output"))
    )
    (net (code "44") (name "Net-(U5-!HOLD)") (class "Default")
      (node (ref "R43") (pin "1") (pinfunction "1_1") (pintype "passive"))
      (node (ref "U5") (pin "7") (pinfunction "!HOLD_7") (pintype "input"))
    )
    (net (code "45") (name "Net-(U5-!WP)") (class "Default")
      (node (ref "R42") (pin "1") (pinfunction "1_1") (pintype "passive"))
      (node (ref "U5") (pin "3") (pinfunction "!WP_3") (pintype "input"))
    )
    (net (code "46") (name "Net-(U6-CELL)") (class "Default")
      (node (ref "C54") (pin "2") (pinfunction "2_2") (pintype "passive"))
      (node (ref "R54") (pin "1") (pinfunction "1_1") (pintype "passive"))
      (node (ref "U6") (pin "B3") (pinfunction "CELL_B3") (pintype "power_in"))
    )
    (net (code "47") (name "Net-(U6-Vdd)") (class "Default")
      (node (ref "C53") (pin "1") (pinfunction "1_1") (pintype "passive"))
      (node (ref "R56") (pin "2") (pinfunction "2_2") (pintype "passive"))
      (node (ref "U6") (pin "C2") (pinfunction "Vdd_C2") (pintype "power_in"))
    )
    (net (code "48") (name "Net-(U7-SW)") (class "Default")
      (node (ref "L4") (pin "1") (pinfunction "1_1") (pintype "passive"))
      (node (ref "U7") (pin "2") (pinfunction "SW_2") (pintype "output"))
    )
    (net (code "49") (name "Net-(U8-VREF)") (class "Default")
      (node (ref "C30") (pin "2") (pinfunction "2_2") (pintype "passive"))
      (node (ref "U8") (pin "15") (pinfunction "VREF_15") (pintype "passive"))
    )
    (net (code "50") (name "Net-(U9-L)") (class "Default")
      (node (ref "L3") (pin "2") (pinfunction "2_2") (pintype "passive"))
      (node (ref "U9") (pin "5") (pinfunction "L_5") (pintype "passive"))
    )
    (net (code "51") (name "Net-(U10-DCOUPL)") (class "Default")
      (node (ref "C15") (pin "2") (pinfunction "2_2") (pintype "passive"))
      (node (ref "U10") (pin "23") (pinfunction "DCOUPL_23") (pintype "passive"))
    )
    (net (code "52") (name "Net-(a1-FEED1)") (class "Default")
      (node (ref "C69") (pin "1") (pinfunction "1_1") (pintype "passive"))
      (node (ref "a1") (pin "1") (pinfunction "FEED1_1") (pintype "bidirectional"))
    )
    (net (code "53") (name "VDD") (class "Default")
      (node (ref "C10") (pin "1") (pinfunction "1_1") (pintype "passive"))
      (node (ref "C11") (pin "2") (pinfunction "2_2") (pintype "passive"))
      (node (ref "C22") (pin "2") (pinfunction "2_2") (pintype "passive"))
      (node (ref "C23") (pin "2") (pinfunction "2_2") (pintype "passive"))
      (node (ref "C25") (pin "1") (pinfunction "1_1") (pintype "passive"))
      (node (ref "C33") (pin "2") (pinfunction "2_2") (pintype "passive"))
      (node (ref "C4") (pin "2") (pinfunction "2_2") (pintype "passive"))
      (node (ref "C5") (pin "2") (pinfunction "2_2") (pintype "passive"))
      (node (ref "C51") (pin "2") (pinfunction "2_2") (pintype "passive"))
      (node (ref "C6") (pin "2") (pinfunction "2_2") (pintype "passive"))
      (node (ref "C62") (pin "2") (pinfunction "2_2") (pintype "passive"))
      (node (ref "C7") (pin "2") (pinfunction "2_2") (pintype "passive"))
      (node (ref "C71") (pin "2") (pinfunction "2_2") (pintype "passive"))
      (node (ref "C8") (pin "2") (pinfunction "2_2") (pintype "passive"))
      (node (ref "L2") (pin "2") (pinfunction "2_2") (pintype "passive"))
      (node (ref "L3") (pin "1") (pinfunction "1_1") (pintype "passive"))
      (node (ref "R10") (pin "2") (pinfunction "2_2") (pintype "passive"))
      (node (ref "R41") (pin "2") (pinfunction "2_2") (pintype "passive"))
      (node (ref "R42") (pin "2") (pinfunction "2_2") (pintype "passive"))
      (node (ref "R43") (pin "2") (pinfunction "2_2") (pintype "passive"))
      (node (ref "R8") (pin "2") (pinfunction "2_2") (pintype "passive"))
      (node (ref "R9") (pin "2") (pinfunction "2_2") (pintype "passive"))
      (node (ref "U10") (pin "13") (pinfunction "VDDS2_13") (pintype "passive"))
      (node (ref "U10") (pin "22") (pinfunction "VDDS3_22") (pintype "passive"))
      (node (ref "U10") (pin "34") (pinfunction "VDDS_DCDC_34") (pintype "passive"))
      (node (ref "U10") (pin "44") (pinfunction "VDDS_44") (pintype "passive"))
      (node (ref "U11") (pin "1") (pinfunction "VDD_1") (pintype "passive"))
      (node (ref "U11") (pin "2") (pinfunction "VDD_2") (pintype "passive"))
      (node (ref "U11") (pin "3") (pinfunction "VDD_3") (pintype "passive"))
      (node (ref "U3") (pin "5") (pinfunction "VOUT_5") (pintype "power_in"))
      (node (ref "U4") (pin "1") (pinfunction "VDDIO_1") (pintype "power_in"))
      (node (ref "U4") (pin "22") (pinfunction "VDD_22") (pintype "passive"))
      (node (ref "U4") (pin "23") (pinfunction "VDD_23") (pintype "passive"))
      (node (ref "U4") (pin "3") (pinfunction "VDDIO_3") (pintype "power_in"))
      (node (ref "U4") (pin "7") (pinfunction "CS_A/G_7") (pintype "input"))
      (node (ref "U4") (pin "8") (pinfunction "CS_M_8") (pintype "input"))
      (node (ref "U5") (pin "8") (pinfunction "VCC_8") (pintype "power_in"))
      (node (ref "U7") (pin "1") (pinfunction "VIN_1") (pintype "power_in"))
      (node (ref "U7") (pin "12") (pinfunction "EN_12") (pintype "input"))
      (node (ref "U9") (pin "4") (pinfunction "EN_4") (pintype "passive"))
      (node (ref "U9") (pin "6") (pinfunction "VIN_6") (pintype "passive"))
    )
    (net (code "54") (name "unconnected-(K3--AD-EN-Pad8)") (class "Default")
      (node (ref "K3") (pin "8") (pinfunction "-AD-EN_8") (pintype "bidirectional"))
    )
    (net (code "55") (name "unconnected-(K3-EN2-Pad11)") (class "Default")
      (node (ref "K3") (pin "11") (pinfunction "EN2_11") (pintype "bidirectional"))
    )
    (net (code "56") (name "unconnected-(U3-LOAD-Pad6)") (class "Default")
      (node (ref "U3") (pin "6") (pinfunction "LOAD_6") (pintype "bidirectional"))
    )
    (net (code "57") (name "unconnected-(U4-DATA_EN_A{slash}G-Pad13)") (class "Default")
      (node (ref "U4") (pin "13") (pinfunction "DATA_EN_A/G_13") (pintype "input"))
    )
    (net (code "58") (name "unconnected-(U4-DRDY_M-Pad9)") (class "Default")
      (node (ref "U4") (pin "9") (pinfunction "DRDY_M_9") (pintype "output"))
    )
    (net (code "59") (name "unconnected-(U4-INT1_A{slash}G-Pad11)") (class "Default")
      (node (ref "U4") (pin "11") (pinfunction "INT1_A/G_11") (pintype "output"))
    )
    (net (code "60") (name "unconnected-(U4-INT2_A{slash}G-Pad12)") (class "Default")
      (node (ref "U4") (pin "12") (pinfunction "INT2_A/G_12") (pintype "output"))
    )
    (net (code "61") (name "unconnected-(U4-INT_M-Pad10)") (class "Default")
      (node (ref "U4") (pin "10") (pinfunction "INT_M_10") (pintype "output"))
    )
    (net (code "62") (name "unconnected-(U7-LOAD-Pad6)") (class "Default")
      (node (ref "U7") (pin "6") (pinfunction "LOAD_6") (pintype "bidirectional"))
    )
    (net (code "63") (name "unconnected-(U7-PG-Pad7)") (class "Default")
      (node (ref "U7") (pin "7") (pinfunction "PG_7") (pintype "bidirectional"))
    )
    (net (code "64") (name "unconnected-(U8-INTB-Pad5)") (class "Default")
      (node (ref "U8") (pin "5") (pinfunction "INTB_5") (pintype "passive"))
    )
    (net (code "65") (name "unconnected-(U8-NC_1-Pad1)") (class "Default")
      (node (ref "U8") (pin "1") (pinfunction "NC_1_1") (pintype "passive"))
    )
    (net (code "66") (name "unconnected-(U8-NC_2-Pad2)") (class "Default")
      (node (ref "U8") (pin "2") (pinfunction "NC_2_2") (pintype "passive"))
    )
    (net (code "67") (name "unconnected-(U8-NC_3-Pad3)") (class "Default")
      (node (ref "U8") (pin "3") (pinfunction "NC_3_3") (pintype "passive"))
    )
    (net (code "68") (name "unconnected-(U8-NC_4-Pad4)") (class "Default")
      (node (ref "U8") (pin "4") (pinfunction "NC_4_4") (pintype "passive"))
    )
    (net (code "69") (name "unconnected-(U8-NC_5-Pad8)") (class "Default")
      (node (ref "U8") (pin "8") (pinfunction "NC_5_8") (pintype "passive"))
    )
    (net (code "70") (name "unconnected-(U8-NC_6-Pad9)") (class "Default")
      (node (ref "U8") (pin "9") (pinfunction "NC_6_9") (pintype "passive"))
    )
    (net (code "71") (name "unconnected-(U8-NC_7-Pad10)") (class "Default")
      (node (ref "U8") (pin "10") (pinfunction "NC_7_10") (pintype "passive"))
    )
    (net (code "72") (name "unconnected-(U8-NC_8-Pad16)") (class "Default")
      (node (ref "U8") (pin "16") (pinfunction "NC_8_16") (pintype "passive"))
    )
    (net (code "73") (name "unconnected-(U8-NC_9-Pad17)") (class "Default")
      (node (ref "U8") (pin "17") (pinfunction "NC_9_17") (pintype "passive"))
    )
    (net (code "74") (name "unconnected-(U8-NC_10-Pad18)") (class "Default")
      (node (ref "U8") (pin "18") (pinfunction "NC_10_18") (pintype "passive"))
    )
    (net (code "75") (name "unconnected-(U10-D0-Pad5)") (class "Default")
      (node (ref "U10") (pin "5") (pinfunction "D0_5") (pintype "passive"))
    )
    (net (code "76") (name "unconnected-(U10-D1-Pad6)") (class "Default")
      (node (ref "U10") (pin "6") (pinfunction "D1_6") (pintype "passive"))
    )
    (net (code "77") (name "unconnected-(U10-D2-Pad7)") (class "Default")
      (node (ref "U10") (pin "7") (pinfunction "D2_7") (pintype "passive"))
    )
    (net (code "78") (name "unconnected-(U10-D3-Pad8)") (class "Default")
      (node (ref "U10") (pin "8") (pinfunction "D3_8") (pintype "passive"))
    )
    (net (code "79") (name "unconnected-(U10-D7-Pad12)") (class "Default")
      (node (ref "U10") (pin "12") (pinfunction "D7_12") (pintype "passive"))
    )
    (net (code "80") (name "unconnected-(U10-D12-Pad18)") (class "Default")
      (node (ref "U10") (pin "18") (pinfunction "D12_18") (pintype "passive"))
    )
    (net (code "81") (name "unconnected-(U10-D13-Pad19)") (class "Default")
      (node (ref "U10") (pin "19") (pinfunction "D13_19") (pintype "passive"))
    )
    (net (code "82") (name "unconnected-(U10-D14-Pad20)") (class "Default")
      (node (ref "U10") (pin "20") (pinfunction "D14_20") (pintype "passive"))
    )
    (net (code "83") (name "unconnected-(U10-D15-Pad21)") (class "Default")
      (node (ref "U10") (pin "21") (pinfunction "D15_21") (pintype "passive"))
    )
    (net (code "84") (name "unconnected-(U10-D16-Pad26)") (class "Default")
      (node (ref "U10") (pin "26") (pinfunction "D16_26") (pintype "passive"))
    )
    (net (code "85") (name "unconnected-(U10-D17-Pad27)") (class "Default")
      (node (ref "U10") (pin "27") (pinfunction "D17_27") (pintype "passive"))
    )
    (net (code "86") (name "unconnected-(U10-D18-Pad28)") (class "Default")
      (node (ref "U10") (pin "28") (pinfunction "D18_28") (pintype "passive"))
    )
    (net (code "87") (name "unconnected-(U10-D19-Pad29)") (class "Default")
      (node (ref "U10") (pin "29") (pinfunction "D19_29") (pintype "passive"))
    )
    (net (code "88") (name "unconnected-(U10-D20-Pad30)") (class "Default")
      (node (ref "U10") (pin "30") (pinfunction "D20_30") (pintype "passive"))
    )
    (net (code "89") (name "unconnected-(U10-D21-Pad31)") (class "Default")
      (node (ref "U10") (pin "31") (pinfunction "D21_31") (pintype "passive"))
    )
    (net (code "90") (name "unconnected-(U10-D22-Pad32)") (class "Default")
      (node (ref "U10") (pin "32") (pinfunction "D22_32") (pintype "passive"))
    )
    (net (code "91") (name "unconnected-(U10-D24-Pad37)") (class "Default")
      (node (ref "U10") (pin "37") (pinfunction "D24_37") (pintype "passive"))
    )
    (net (code "92") (name "unconnected-(U10-D25-Pad38)") (class "Default")
      (node (ref "U10") (pin "38") (pinfunction "D25_38") (pintype "passive"))
    )
    (net (code "93") (name "unconnected-(U10-D26-Pad39)") (class "Default")
      (node (ref "U10") (pin "39") (pinfunction "D26_39") (pintype "passive"))
    )
    (net (code "94") (name "unconnected-(U10-D27-Pad40)") (class "Default")
      (node (ref "U10") (pin "40") (pinfunction "D27_40") (pintype "passive"))
    )
    (net (code "95") (name "unconnected-(U10-D28-Pad41)") (class "Default")
      (node (ref "U10") (pin "41") (pinfunction "D28_41") (pintype "passive"))
    )
    (net (code "96") (name "unconnected-(U10-D30-Pad43)") (class "Default")
      (node (ref "U10") (pin "43") (pinfunction "D30_43") (pintype "passive"))
    )
    (net (code "97") (name "unconnected-(U10-X32_1-Pad3)") (class "Default")
      (node (ref "U10") (pin "3") (pinfunction "X32_1_3") (pintype "passive"))
    )
    (net (code "98") (name "unconnected-(U10-X32_2-Pad4)") (class "Default")
      (node (ref "U10") (pin "4") (pinfunction "X32_2_4") (pintype "passive"))
    )
    (net (code "99") (name "unconnected-(U11-GPIO00-Pad10)") (class "Default")
      (node (ref "U11") (pin "10") (pinfunction "GPIO00_10") (pintype "passive"))
    )
    (net (code "100") (name "unconnected-(U11-GPIO1-Pad7)") (class "Default")
      (node (ref "U11") (pin "7") (pinfunction "GPIO1_7") (pintype "passive"))
    )
    (net (code "101") (name "unconnected-(a1-GND-Pad2)") (class "Default")
      (node (ref "a1") (pin "2") (pinfunction "GND_2") (pintype "power_in"))
    )
    (net (code "102") (name "unconnected-(k4-Pad10)") (class "Default")
      (node (ref "k4") (pin "10") (pintype "passive"))
    )
    (net (code "103") (name "unconnected-(k4-Pad11)") (class "Default")
      (node (ref "k4") (pin "11") (pintype "power_in"))
    )
    (net (code "104") (name "unconnected-(k4-Pad12)") (class "Default")
      (node (ref "k4") (pin "12") (pintype "power_in"))
    )
    (net (code "105") (name "unconnected-(k4-Pad13)") (class "Default")
      (node (ref "k4") (pin "13") (pintype "passive"))
    )
    (net (code "106") (name "unconnected-(k4-Pad14)") (class "Default")
      (node (ref "k4") (pin "14") (pintype "passive"))
    )
  )
)
